# VFD_Ura_Controll.net
KiCad netlist of a schematic drawn in Altium Designer
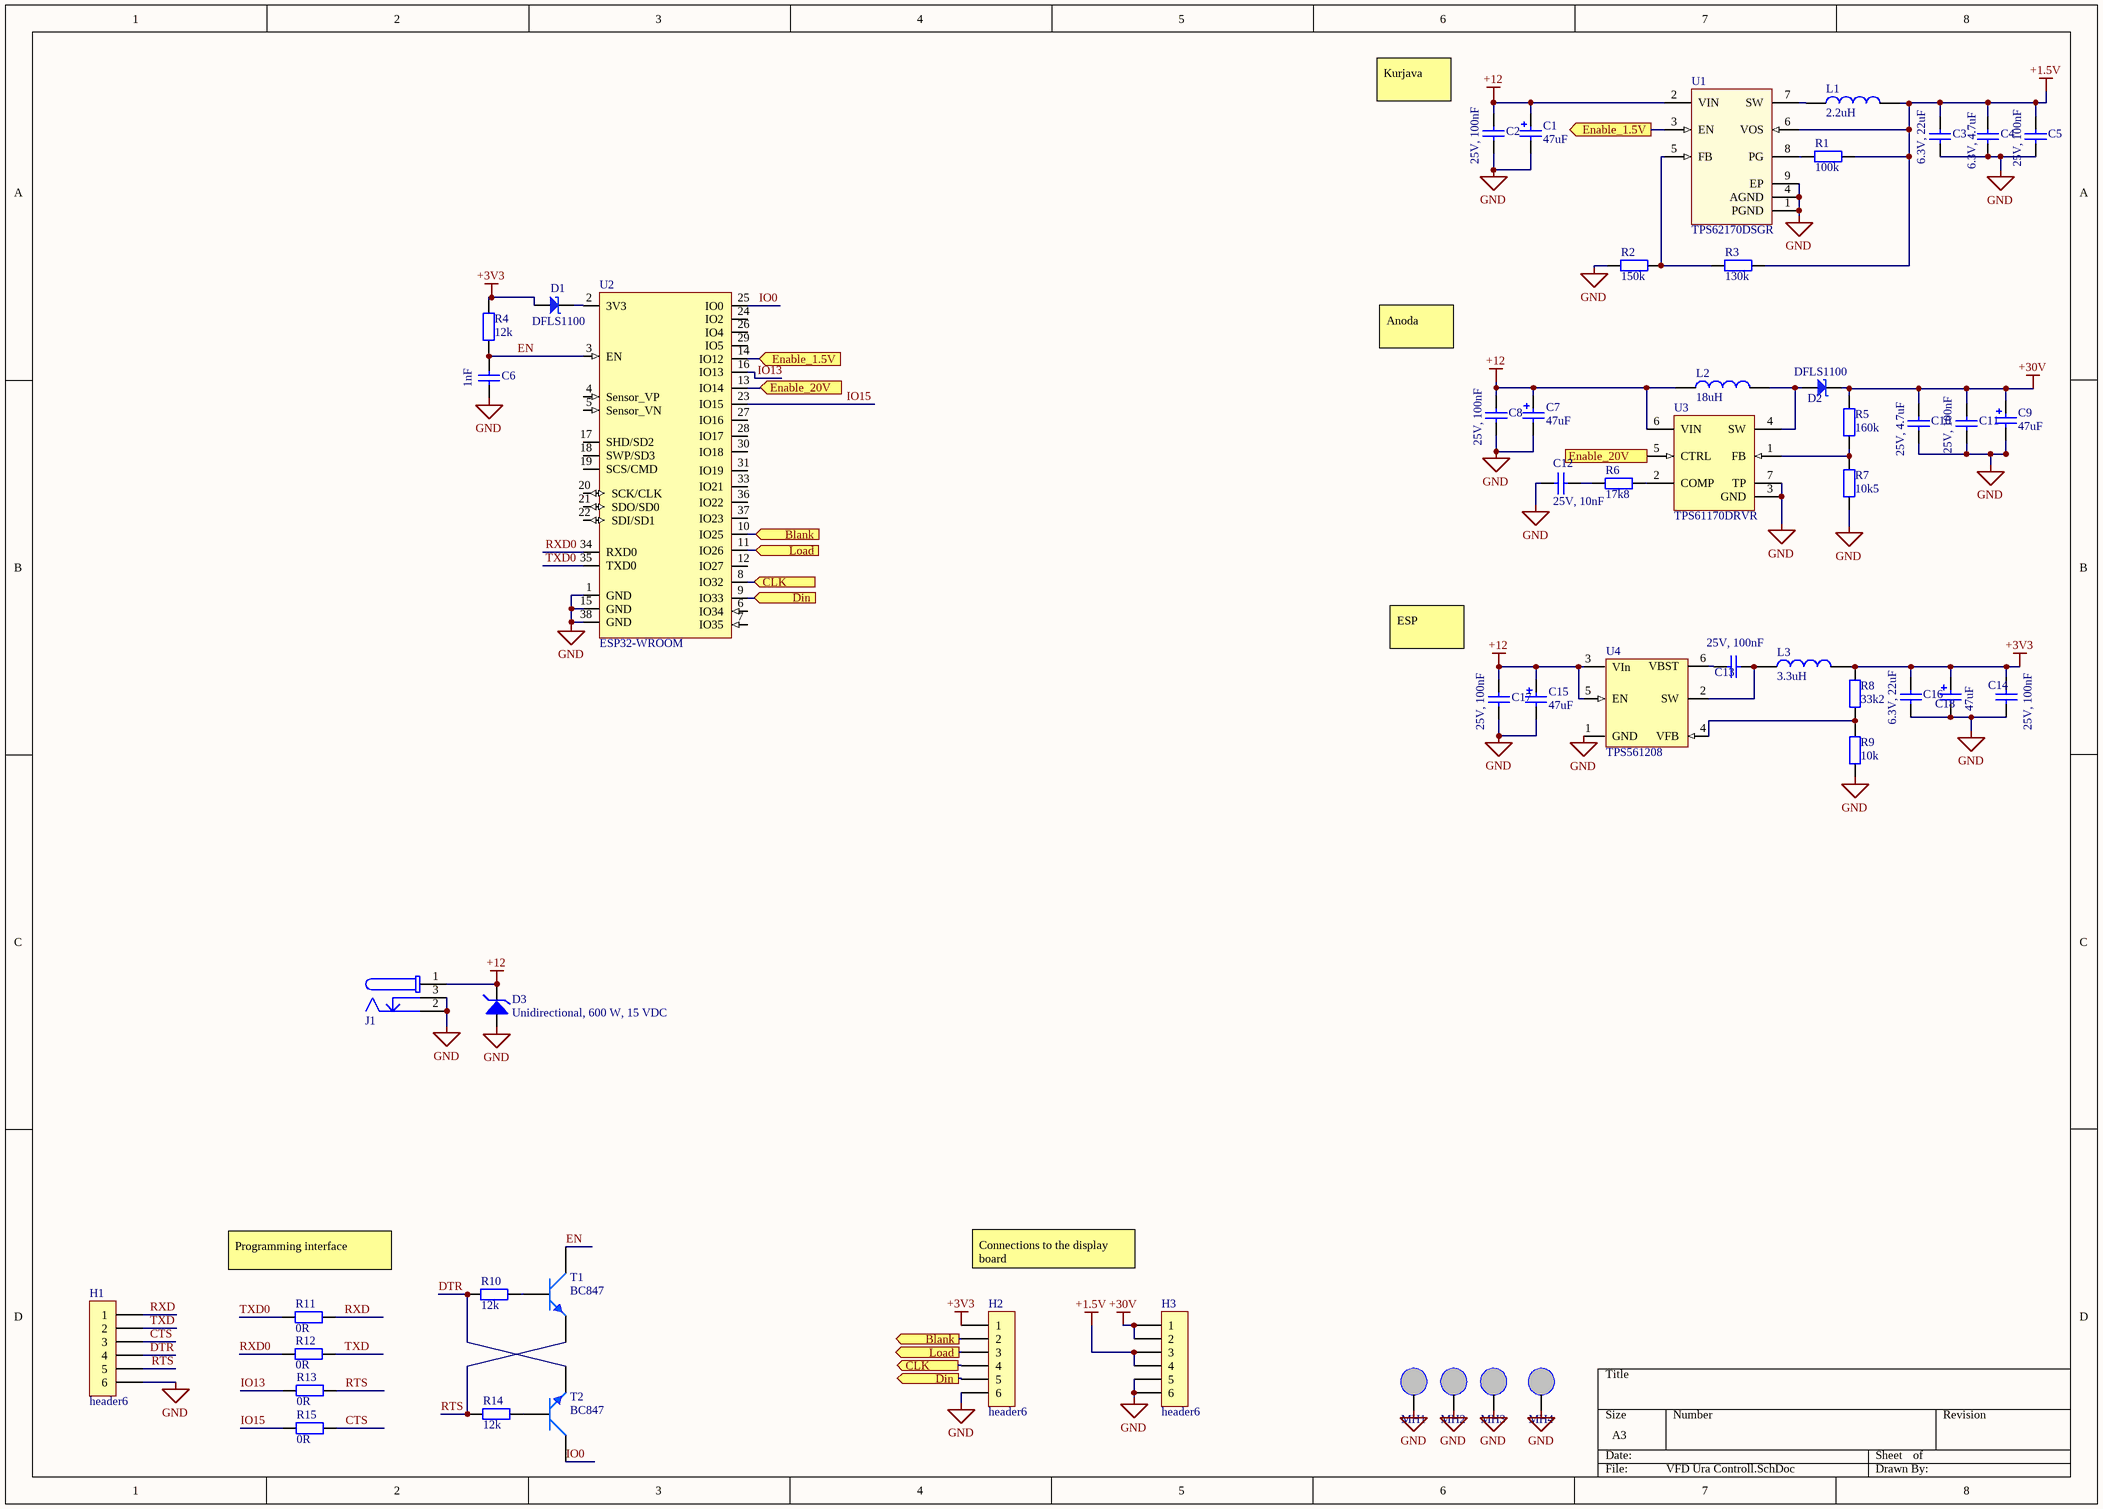
[diagram p0: VFD Ura Controll.SchDoc]

(export (version "E")
  (design (tool "Eeschema 10.0.6"))
  (components
    (comp (ref "C1")
      (value "47uF")
      (footprint "WCAP-PSLC_8x11.7")
      (description "WCAP-PSLC Aluminum Polymer Capacitors, size Ф8x11.7mm, 25V DC, 47uF")
      (fields (field (name "PART NUMBER") "875075555002") (field (name "PUBLISHER") "Wurth Elektronik"))
      (libsource (lib "ALTIUM-WCAP-PSLC-rev17b") (part "875075555002"))
    )
    (comp (ref "C2")
      (value "25V, 100nF")
      (footprint "0603_1.6x0.8x0.8mm_Reflow Soldering")
      (description "WCAP-CSGP Ceramic Capacitors, 0603, X7R, 25V, 100nF")
      (fields (field (name "PART NUMBER") "885012206071") (field (name "PUBLISHER") "Wurth Elektronik"))
      (libsource (lib "ALTIUM-WCAP-CSGP-0603-rev17b") (part "885012206071"))
    )
    (comp (ref "C3")
      (value "6.3V, 22uF")
      (footprint "0805_2x1.25x1.25mm_Reflow Soldering")
      (description "WCAP-CSGP Ceramic Capacitors, 0805, X5R, 6.3V, 22uF")
      (fields (field (name "PART NUMBER") "885012107005") (field (name "PUBLISHER") "Wurth Elektronik"))
      (libsource (lib "ALTIUM-WCAP-CSGP-0805-rev17b") (part "885012107005"))
    )
    (comp (ref "C4")
      (value "6.3V, 4.7uF")
      (footprint "0805_2x1.25x1.25mm_Reflow Soldering")
      (description "WCAP-CSGP Ceramic Capacitors, 0805, X5R, 6.3V, 4.7uF")
      (fields (field (name "PART NUMBER") "885012107003") (field (name "PUBLISHER") "Wurth Elektronik"))
      (libsource (lib "ALTIUM-WCAP-CSGP-0805-rev17b") (part "885012107003"))
    )
    (comp (ref "C5")
      (value "25V, 100nF")
      (footprint "0603_1.6x0.8x0.8mm_Reflow Soldering")
      (description "WCAP-CSGP Ceramic Capacitors, 0603, X7R, 25V, 100nF")
      (fields (field (name "PART NUMBER") "885012206071") (field (name "PUBLISHER") "Wurth Elektronik"))
      (libsource (lib "ALTIUM-WCAP-CSGP-0603-rev17b") (part "885012206071"))
    )
    (comp (ref "C6")
      (value "1nF")
      (footprint "0603_1.6x0.8x0.8mm_Reflow Soldering")
      (description "WCAP-CSGP Ceramic Capacitors, 0603, X7R, 25V, 100nF")
      (fields (field (name "PART NUMBER") "885012206071") (field (name "PUBLISHER") "Wurth Elektronik"))
      (libsource (lib "ALTIUM-WCAP-CSGP-0603-rev17b") (part "885012206071"))
    )
    (comp (ref "C7")
      (value "47uF")
      (footprint "WCAP-PSLC_8x11.7")
      (description "WCAP-PSLC Aluminum Polymer Capacitors, size Ф8x11.7mm, 25V DC, 47uF")
      (fields (field (name "PART NUMBER") "875075555002") (field (name "PUBLISHER") "Wurth Elektronik"))
      (libsource (lib "ALTIUM-WCAP-PSLC-rev17b") (part "875075555002"))
    )
    (comp (ref "C8")
      (value "25V, 100nF")
      (footprint "0603_1.6x0.8x0.8mm_Reflow Soldering")
      (description "WCAP-CSGP Ceramic Capacitors, 0603, X7R, 25V, 100nF")
      (fields (field (name "PART NUMBER") "885012206071") (field (name "PUBLISHER") "Wurth Elektronik"))
      (libsource (lib "ALTIUM-WCAP-CSGP-0603-rev17b") (part "885012206071"))
    )
    (comp (ref "C9")
      (value "47uF")
      (footprint "WCAP-PSLC_8x11.7")
      (description "WCAP-PSLC Aluminum Polymer Capacitors, size Ф8x11.7mm, 25V DC, 47uF")
      (fields (field (name "PART NUMBER") "875075555002") (field (name "PUBLISHER") "Wurth Elektronik"))
      (libsource (lib "ALTIUM-WCAP-PSLC-rev17b") (part "875075555002"))
    )
    (comp (ref "C10")
      (value "25V, 4.7uF")
      (footprint "0805_2x1.25x1.25mm_Reflow Soldering")
      (description "WCAP-CSGP Ceramic Capacitors, 0805, X5R, 25V, 4.7uF")
      (fields (field (name "PART NUMBER") "885012107018") (field (name "PUBLISHER") "Wurth Elektronik"))
      (libsource (lib "ALTIUM-WCAP-CSGP-0805-rev17b") (part "885012107018"))
    )
    (comp (ref "C11")
      (value "25V, 100nF")
      (footprint "0603_1.6x0.8x0.8mm_Reflow Soldering")
      (description "WCAP-CSGP Ceramic Capacitors, 0603, X7R, 25V, 100nF")
      (fields (field (name "PART NUMBER") "885012206071") (field (name "PUBLISHER") "Wurth Elektronik"))
      (libsource (lib "ALTIUM-WCAP-CSGP-0603-rev17b") (part "885012206071"))
    )
    (comp (ref "C12")
      (value "25V, 10nF")
      (footprint "0603_1.6x0.8x0.8mm_Reflow Soldering")
      (description "WCAP-CSGP Ceramic Capacitors, 0603, X7R, 25V, 10nF")
      (fields (field (name "PART NUMBER") "885012206065") (field (name "PUBLISHER") "Wurth Elektronik"))
      (libsource (lib "ALTIUM-WCAP-CSGP-0603-rev17b") (part "885012206065"))
    )
    (comp (ref "C13")
      (value "25V, 100nF")
      (footprint "0603_1.6x0.8x0.8mm_Reflow Soldering")
      (description "WCAP-CSGP Ceramic Capacitors, 0603, X7R, 25V, 100nF")
      (fields (field (name "PART NUMBER") "885012206071") (field (name "PUBLISHER") "Wurth Elektronik"))
      (libsource (lib "ALTIUM-WCAP-CSGP-0603-rev17b") (part "885012206071"))
    )
    (comp (ref "C14")
      (value "25V, 100nF")
      (footprint "0603_1.6x0.8x0.8mm_Reflow Soldering")
      (description "WCAP-CSGP Ceramic Capacitors, 0603, X7R, 25V, 100nF")
      (fields (field (name "PART NUMBER") "885012206071") (field (name "PUBLISHER") "Wurth Elektronik"))
      (libsource (lib "ALTIUM-WCAP-CSGP-0603-rev17b") (part "885012206071"))
    )
    (comp (ref "C15")
      (value "47uF")
      (footprint "WCAP-PSLC_8x11.7")
      (description "WCAP-PSLC Aluminum Polymer Capacitors, size Ф8x11.7mm, 25V DC, 47uF")
      (fields (field (name "PART NUMBER") "875075555002") (field (name "PUBLISHER") "Wurth Elektronik"))
      (libsource (lib "ALTIUM-WCAP-PSLC-rev17b") (part "875075555002"))
    )
    (comp (ref "C16")
      (value "6.3V, 22uF")
      (footprint "0805_2x1.25x1.25mm_Reflow Soldering")
      (description "WCAP-CSGP Ceramic Capacitors, 0805, X5R, 6.3V, 22uF")
      (fields (field (name "PART NUMBER") "885012107005") (field (name "PUBLISHER") "Wurth Elektronik"))
      (libsource (lib "ALTIUM-WCAP-CSGP-0805-rev17b") (part "885012107005"))
    )
    (comp (ref "C17")
      (value "25V, 100nF")
      (footprint "0603_1.6x0.8x0.8mm_Reflow Soldering")
      (description "WCAP-CSGP Ceramic Capacitors, 0603, X7R, 25V, 100nF")
      (fields (field (name "PART NUMBER") "885012206071") (field (name "PUBLISHER") "Wurth Elektronik"))
      (libsource (lib "ALTIUM-WCAP-CSGP-0603-rev17b") (part "885012206071"))
    )
    (comp (ref "C18")
      (value "47uF")
      (footprint "WCAP-PSLC_8x11.7")
      (description "WCAP-PSLC Aluminum Polymer Capacitors, size Ф8x11.7mm, 25V DC, 47uF")
      (fields (field (name "PART NUMBER") "875075555002") (field (name "PUBLISHER") "Wurth Elektronik"))
      (libsource (lib "ALTIUM-WCAP-PSLC-rev17b") (part "875075555002"))
    )
    (comp (ref "D1")
      (value "DFLS1100")
      (footprint "PowerDi123")
      (libsource (lib "Oblak Library") (part "DFLS1100"))
    )
    (comp (ref "D2")
      (value "DFLS1100")
      (footprint "PowerDi123")
      (libsource (lib "Oblak Library") (part "DFLS1100"))
    )
    (comp (ref "D3")
      (value "Unidirectional, 600 W, 15 VDC")
      (footprint "DO-214AA_Unidirectional")
      (description "WE-TVSP Power TVS Diode, Unidirectional, 600 W, 15 VDC")
      (fields
        (field (name "PARTNO") "824520151")
        (field (name "MANUFACTURER") "Wurth Elektronik")
        (field (name "CREATED BY") "Baojun Chen")
      )
      (libsource (lib "ALTIUM-WE-TVSP-rev15a") (part "WE-TVSP DO-214AA, 824520151"))
    )
    (comp (ref "H1") (value "header6") (footprint "Letev6") (libsource (lib "VolkD3D") (part "header6")))
    (comp (ref "H2") (value "header6") (footprint "Letev6") (libsource (lib "") (part "header6_1")))
    (comp (ref "H3") (value "header6") (footprint "Letev6") (libsource (lib "") (part "header6_1")))
    (comp (ref "J1")
      (value "694106301002")
      (footprint "694106301002")
      (description "DC Power Jack Right Angled(6.4) WR-DC")
      (fields (field (name "PUBLISHER") "Wurth Elektronik"))
      (libsource (lib "Altium_WR-DC_POWER_JACK_CONNECTORS (rev17a)") (part "694106301002"))
    )
    (comp (ref "L1")
      (value "2.2uH")
      (footprint "WE-TPC_2811")
      (description "WE-TPC SMD Shielded Tiny Power Inductor, size 2811, 1.3A, 125mΩ, 2.2uH")
      (fields (field (name "PART NUMBER") "744028002") (field (name "PUBLISHER") "Wurth Elektronik"))
      (libsource (lib "ALTIUM-WE-TPC-rev17a") (part "744028002"))
    )
    (comp (ref "L2")
      (value "18uH")
      (footprint "WE-TPC_4818")
      (description "WE-TPC SMD Shielded Tiny Power Inductor, size 4818, 0.92A, 270mΩ, 18uH")
      (fields (field (name "PART NUMBER") "744042180") (field (name "PUBLISHER") "Wurth Elektronik"))
      (libsource (lib "ALTIUM-WE-TPC-rev17a") (part "744042180"))
    )
    (comp (ref "L3")
      (value "3.3uH")
      (footprint "WE-TPC_2828")
      (description "WE-TPC SMD Shielded Tiny Power Inductor, size 2828, 1.5A, 85mΩ, 3.3uH")
      (fields (field (name "PART NUMBER") "744025003") (field (name "PUBLISHER") "Wurth Elektronik"))
      (libsource (lib "ALTIUM-WE-TPC-rev17a") (part "744025003"))
    )
    (comp (ref "MH1")
      (value "Mounting Hole M3")
      (footprint "Mounting Hole M3")
      (libsource (lib "Oblak Library") (part "Mounting Hole M3"))
    )
    (comp (ref "MH2")
      (value "Mounting Hole M3")
      (footprint "Mounting Hole M3")
      (libsource (lib "Oblak Library") (part "Mounting Hole M3"))
    )
    (comp (ref "MH3")
      (value "Mounting Hole M3")
      (footprint "Mounting Hole M3")
      (libsource (lib "Oblak Library") (part "Mounting Hole M3"))
    )
    (comp (ref "MH4")
      (value "Mounting Hole M3")
      (footprint "Mounting Hole M3")
      (libsource (lib "Oblak Library") (part "Mounting Hole M3"))
    )
    (comp (ref "R1")
      (value "100k")
      (footprint "RES0805_1")
      (fields (field (name "Comment") "Res2-smd"))
      (libsource (lib "VolkD3D") (part "Res2-smd"))
    )
    (comp (ref "R2")
      (value "150k")
      (footprint "RES0805_1")
      (fields (field (name "Comment") "Res2-smd"))
      (libsource (lib "VolkD3D") (part "Res2-smd"))
    )
    (comp (ref "R3")
      (value "130k")
      (footprint "RES0805_1")
      (fields (field (name "Comment") "Res2-smd"))
      (libsource (lib "VolkD3D") (part "Res2-smd"))
    )
    (comp (ref "R4") (value "12k") (footprint "RES0805_1") (libsource (lib "") (part "Res2-smd_1")))
    (comp (ref "R5")
      (value "160k")
      (footprint "RES0805_1")
      (fields (field (name "Comment") "Res2-smd"))
      (libsource (lib "") (part "Res2-smd_1"))
    )
    (comp (ref "R6")
      (value "17k8")
      (footprint "RES0805_1")
      (fields (field (name "Comment") "Res2-smd"))
      (libsource (lib "VolkD3D") (part "Res2-smd"))
    )
    (comp (ref "R7")
      (value "10k5")
      (footprint "RES0805_1")
      (fields (field (name "Comment") "Res2-smd"))
      (libsource (lib "") (part "Res2-smd_1"))
    )
    (comp (ref "R8")
      (value "33k2")
      (footprint "RES0805_1")
      (fields (field (name "Comment") "Res2-smd"))
      (libsource (lib "") (part "Res2-smd_1"))
    )
    (comp (ref "R9")
      (value "10k")
      (footprint "RES0805_1")
      (fields (field (name "Comment") "Res2-smd"))
      (libsource (lib "") (part "Res2-smd_1"))
    )
    (comp (ref "R10") (value "12k") (footprint "RES0805_1") (libsource (lib "") (part "Res2-smd_2")))
    (comp (ref "R11")
      (value "0R")
      (footprint "RES0805_1")
      (fields (field (name "Comment") "12k"))
      (libsource (lib "") (part "Res2-smd_2"))
    )
    (comp (ref "R12")
      (value "0R")
      (footprint "RES0805_1")
      (fields (field (name "Comment") "12k"))
      (libsource (lib "") (part "Res2-smd_2"))
    )
    (comp (ref "R13")
      (value "0R")
      (footprint "RES0805_1")
      (fields (field (name "Comment") "12k"))
      (libsource (lib "") (part "Res2-smd_2"))
    )
    (comp (ref "R14") (value "12k") (footprint "RES0805_1") (libsource (lib "") (part "Res2-smd_2")))
    (comp (ref "R15")
      (value "0R")
      (footprint "RES0805_1")
      (fields (field (name "Comment") "12k"))
      (libsource (lib "") (part "Res2-smd_2"))
    )
    (comp (ref "T1")
      (value "BC847")
      (footprint "SOT23")
      (description "45 V, 100 mA NPN general-purpose transistors")
      (libsource (lib "Oblak Library") (part "BC847"))
    )
    (comp (ref "T2")
      (value "BC847")
      (footprint "SOT23")
      (description "45 V, 100 mA NPN general-purpose transistors")
      (libsource (lib "Oblak Library") (part "BC847"))
    )
    (comp (ref "U1")
      (value "TPS62170DSGR")
      (footprint "DSG8-1600X900TP")
      (fields (field (name "MANUFACTURER") "Texas Instruments"))
      (libsource (lib "TI Power Management Step-Down Regulator") (part "TPS62170DSGR"))
    )
    (comp (ref "U2")
      (value "ESP32-WROOM")
      (footprint "ESP32-WROOM")
      (libsource (lib "IV-6") (part "ESP32-WROOM"))
    )
    (comp (ref "U3")
      (value "TPS61170DRVR")
      (footprint "DRV6-1600X1000TP")
      (fields (field (name "MANUFACTURER") "Texas Instruments"))
      (libsource (lib "TI Power Management Step-Up Regulator") (part "TPS61170DRVR"))
    )
    (comp (ref "U4")
      (value "TPS561208")
      (footprint "SOT23-6 TI")
      (libsource (lib "Oblak Library") (part "TPS561208"))
    )
  )
  (nets
    (net (code "1") (name "+1.5V") (class "Default")
      (node (ref "C3") (pin "2") (pinfunction "2_2") (pintype "passive"))
      (node (ref "C4") (pin "2") (pinfunction "2_2") (pintype "passive"))
      (node (ref "C5") (pin "2") (pinfunction "2_2") (pintype "passive"))
      (node (ref "H3") (pin "3") (pinfunction "3_3") (pintype "passive"))
      (node (ref "H3") (pin "4") (pinfunction "4_4") (pintype "passive"))
      (node (ref "L1") (pin "2") (pinfunction "2_2") (pintype "passive"))
      (node (ref "R1") (pin "2") (pinfunction "2_2") (pintype "passive"))
      (node (ref "R3") (pin "2") (pinfunction "2_2") (pintype "passive"))
      (node (ref "U1") (pin "6") (pinfunction "VOS_6") (pintype "input"))
    )
    (net (code "2") (name "+3V3") (class "Default")
      (node (ref "C14") (pin "2") (pinfunction "2_2") (pintype "passive"))
      (node (ref "C16") (pin "2") (pinfunction "2_2") (pintype "passive"))
      (node (ref "C18") (pin "1") (pinfunction "P_1") (pintype "passive"))
      (node (ref "D1") (pin "1") (pinfunction "A_1") (pintype "passive"))
      (node (ref "H2") (pin "1") (pinfunction "1_1") (pintype "passive"))
      (node (ref "L3") (pin "2") (pinfunction "2_2") (pintype "passive"))
      (node (ref "R4") (pin "2") (pinfunction "2_2") (pintype "passive"))
      (node (ref "R8") (pin "2") (pinfunction "2_2") (pintype "passive"))
    )
    (net (code "3") (name "+12") (class "Default")
      (node (ref "C1") (pin "1") (pinfunction "P_1") (pintype "passive"))
      (node (ref "C15") (pin "1") (pinfunction "P_1") (pintype "passive"))
      (node (ref "C17") (pin "2") (pinfunction "2_2") (pintype "passive"))
      (node (ref "C2") (pin "2") (pinfunction "2_2") (pintype "passive"))
      (node (ref "C7") (pin "1") (pinfunction "P_1") (pintype "passive"))
      (node (ref "C8") (pin "2") (pinfunction "2_2") (pintype "passive"))
      (node (ref "D3") (pin "1") (pinfunction "1_1") (pintype "passive"))
      (node (ref "J1") (pin "1") (pinfunction "1_1") (pintype "passive"))
      (node (ref "L2") (pin "1") (pinfunction "1_1") (pintype "passive"))
      (node (ref "U1") (pin "2") (pinfunction "VIN_2") (pintype "power_in"))
      (node (ref "U3") (pin "6") (pinfunction "VIN_6") (pintype "power_in"))
      (node (ref "U4") (pin "3") (pinfunction "VIn_3") (pintype "power_in"))
      (node (ref "U4") (pin "5") (pinfunction "EN_5") (pintype "input"))
    )
    (net (code "4") (name "+30V") (class "Default")
      (node (ref "C10") (pin "2") (pinfunction "2_2") (pintype "passive"))
      (node (ref "C11") (pin "2") (pinfunction "2_2") (pintype "passive"))
      (node (ref "C9") (pin "1") (pinfunction "P_1") (pintype "passive"))
      (node (ref "D2") (pin "2") (pinfunction "K_2") (pintype "passive"))
      (node (ref "H3") (pin "1") (pinfunction "1_1") (pintype "passive"))
      (node (ref "H3") (pin "2") (pinfunction "2_2") (pintype "passive"))
      (node (ref "R5") (pin "2") (pinfunction "2_2") (pintype "passive"))
    )
    (net (code "5") (name "/Blank") (class "Default")
      (node (ref "H2") (pin "2") (pinfunction "2_2") (pintype "passive"))
      (node (ref "U2") (pin "10") (pinfunction "IO25_10") (pintype "bidirectional"))
    )
    (net (code "6") (name "/CLK") (class "Default")
      (node (ref "H2") (pin "4") (pinfunction "4_4") (pintype "passive"))
      (node (ref "U2") (pin "8") (pinfunction "IO32_8") (pintype "bidirectional"))
    )
    (net (code "7") (name "/CTS") (class "Default")
      (node (ref "H1") (pin "3") (pinfunction "3_3") (pintype "passive"))
      (node (ref "R15") (pin "1") (pinfunction "1_1") (pintype "passive"))
    )
    (net (code "8") (name "/DTR") (class "Default")
      (node (ref "H1") (pin "4") (pinfunction "4_4") (pintype "passive"))
      (node (ref "R10") (pin "2") (pinfunction "2_2") (pintype "passive"))
      (node (ref "T2") (pin "2") (pinfunction "E_2") (pintype "passive"))
    )
    (net (code "9") (name "/Din") (class "Default")
      (node (ref "H2") (pin "5") (pinfunction "5_5") (pintype "passive"))
      (node (ref "U2") (pin "9") (pinfunction "IO33_9") (pintype "bidirectional"))
    )
    (net (code "10") (name "/EN") (class "Default")
      (node (ref "C6") (pin "2") (pinfunction "2_2") (pintype "passive"))
      (node (ref "R4") (pin "1") (pinfunction "1_1") (pintype "passive"))
      (node (ref "T1") (pin "3") (pinfunction "C_3") (pintype "passive"))
      (node (ref "U2") (pin "3") (pinfunction "EN_3") (pintype "input"))
    )
    (net (code "11") (name "/Enable_1.5V") (class "Default")
      (node (ref "U1") (pin "3") (pinfunction "EN_3") (pintype "input"))
      (node (ref "U2") (pin "14") (pinfunction "IO12_14") (pintype "bidirectional"))
    )
    (net (code "12") (name "/Enable_20V") (class "Default")
      (node (ref "U2") (pin "13") (pinfunction "IO14_13") (pintype "bidirectional"))
      (node (ref "U3") (pin "5") (pinfunction "CTRL_5") (pintype "input"))
    )
    (net (code "13") (name "/IO0") (class "Default")
      (node (ref "T2") (pin "3") (pinfunction "C_3") (pintype "passive"))
      (node (ref "U2") (pin "25") (pinfunction "IO0_25") (pintype "bidirectional"))
    )
    (net (code "14") (name "/IO13") (class "Default")
      (node (ref "R13") (pin "2") (pinfunction "2_2") (pintype "passive"))
      (node (ref "U2") (pin "16") (pinfunction "IO13_16") (pintype "bidirectional"))
    )
    (net (code "15") (name "/IO15") (class "Default")
      (node (ref "R15") (pin "2") (pinfunction "2_2") (pintype "passive"))
      (node (ref "U2") (pin "23") (pinfunction "IO15_23") (pintype "bidirectional"))
    )
    (net (code "16") (name "/Load") (class "Default")
      (node (ref "H2") (pin "3") (pinfunction "3_3") (pintype "passive"))
      (node (ref "U2") (pin "11") (pinfunction "IO26_11") (pintype "bidirectional"))
    )
    (net (code "17") (name "/RTS") (class "Default")
      (node (ref "H1") (pin "5") (pinfunction "5_5") (pintype "passive"))
      (node (ref "R13") (pin "1") (pinfunction "1_1") (pintype "passive"))
      (node (ref "R14") (pin "2") (pinfunction "2_2") (pintype "passive"))
      (node (ref "T1") (pin "2") (pinfunction "E_2") (pintype "passive"))
    )
    (net (code "18") (name "/RXD") (class "Default")
      (node (ref "H1") (pin "1") (pinfunction "1_1") (pintype "passive"))
      (node (ref "R11") (pin "1") (pinfunction "1_1") (pintype "passive"))
    )
    (net (code "19") (name "/RXD0") (class "Default")
      (node (ref "R12") (pin "2") (pinfunction "2_2") (pintype "passive"))
      (node (ref "U2") (pin "34") (pinfunction "RXD0_34") (pintype "bidirectional"))
    )
    (net (code "20") (name "/TXD") (class "Default")
      (node (ref "H1") (pin "2") (pinfunction "2_2") (pintype "passive"))
      (node (ref "R12") (pin "1") (pinfunction "1_1") (pintype "passive"))
    )
    (net (code "21") (name "/TXD0") (class "Default")
      (node (ref "R11") (pin "2") (pinfunction "2_2") (pintype "passive"))
      (node (ref "U2") (pin "35") (pinfunction "TXD0_35") (pintype "bidirectional"))
    )
    (net (code "22") (name "GND") (class "Default")
      (node (ref "C1") (pin "2") (pinfunction "N_2") (pintype "passive"))
      (node (ref "C10") (pin "1") (pinfunction "1_1") (pintype "passive"))
      (node (ref "C11") (pin "1") (pinfunction "1_1") (pintype "passive"))
      (node (ref "C12") (pin "1") (pinfunction "1_1") (pintype "passive"))
      (node (ref "C14") (pin "1") (pinfunction "1_1") (pintype "passive"))
      (node (ref "C15") (pin "2") (pinfunction "N_2") (pintype "passive"))
      (node (ref "C16") (pin "1") (pinfunction "1_1") (pintype "passive"))
      (node (ref "C17") (pin "1") (pinfunction "1_1") (pintype "passive"))
      (node (ref "C18") (pin "2") (pinfunction "N_2") (pintype "passive"))
      (node (ref "C2") (pin "1") (pinfunction "1_1") (pintype "passive"))
      (node (ref "C3") (pin "1") (pinfunction "1_1") (pintype "passive"))
      (node (ref "C4") (pin "1") (pinfunction "1_1") (pintype "passive"))
      (node (ref "C5") (pin "1") (pinfunction "1_1") (pintype "passive"))
      (node (ref "C6") (pin "1") (pinfunction "1_1") (pintype "passive"))
      (node (ref "C7") (pin "2") (pinfunction "N_2") (pintype "passive"))
      (node (ref "C8") (pin "1") (pinfunction "1_1") (pintype "passive"))
      (node (ref "C9") (pin "2") (pinfunction "N_2") (pintype "passive"))
      (node (ref "D3") (pin "2") (pinfunction "2_2") (pintype "passive"))
      (node (ref "H1") (pin "6") (pinfunction "6_6") (pintype "passive"))
      (node (ref "H2") (pin "6") (pinfunction "6_6") (pintype "passive"))
      (node (ref "H3") (pin "5") (pinfunction "5_5") (pintype "passive"))
      (node (ref "H3") (pin "6") (pinfunction "6_6") (pintype "passive"))
      (node (ref "J1") (pin "2") (pinfunction "2_2") (pintype "passive"))
      (node (ref "J1") (pin "3") (pinfunction "3_3") (pintype "passive"))
      (node (ref "MH1") (pin "1") (pintype "passive"))
      (node (ref "MH2") (pin "1") (pintype "passive"))
      (node (ref "MH3") (pin "1") (pintype "passive"))
      (node (ref "MH4") (pin "1") (pintype "passive"))
      (node (ref "R2") (pin "1") (pinfunction "1_1") (pintype "passive"))
      (node (ref "R7") (pin "1") (pinfunction "1_1") (pintype "passive"))
      (node (ref "R9") (pin "1") (pinfunction "1_1") (pintype "passive"))
      (node (ref "U1") (pin "1") (pinfunction "PGND_1") (pintype "power_in"))
      (node (ref "U1") (pin "4") (pinfunction "AGND_4") (pintype "power_in"))
      (node (ref "U1") (pin "9") (pinfunction "EP_9") (pintype "power_in"))
      (node (ref "U2") (pin "1") (pinfunction "GND_1") (pintype "power_in"))
      (node (ref "U2") (pin "15") (pinfunction "GND_15") (pintype "power_in"))
      (node (ref "U2") (pin "38") (pinfunction "GND_38") (pintype "power_in"))
      (node (ref "U3") (pin "3") (pinfunction "GND_3") (pintype "power_in"))
      (node (ref "U3") (pin "7") (pinfunction "TP_7") (pintype "power_in"))
      (node (ref "U4") (pin "1") (pinfunction "GND_1") (pintype "power_in"))
    )
    (net (code "23") (name "Net-(C12-Pad2)") (class "Default")
      (node (ref "C12") (pin "2") (pinfunction "2_2") (pintype "passive"))
      (node (ref "R6") (pin "1") (pinfunction "1_1") (pintype "passive"))
    )
    (net (code "24") (name "Net-(D1-K)") (class "Default")
      (node (ref "D1") (pin "2") (pinfunction "K_2") (pintype "passive"))
      (node (ref "U2") (pin "2") (pinfunction "3V3_2") (pintype "power_in"))
    )
    (net (code "25") (name "Net-(D2-A)") (class "Default")
      (node (ref "D2") (pin "1") (pinfunction "A_1") (pintype "passive"))
      (node (ref "L2") (pin "2") (pinfunction "2_2") (pintype "passive"))
      (node (ref "U3") (pin "4") (pinfunction "SW_4") (pintype "power_in"))
    )
    (net (code "26") (name "Net-(T1-B)") (class "Default")
      (node (ref "R10") (pin "1") (pinfunction "1_1") (pintype "passive"))
      (node (ref "T1") (pin "1") (pinfunction "B_1") (pintype "passive"))
    )
    (net (code "27") (name "Net-(T2-B)") (class "Default")
      (node (ref "R14") (pin "1") (pinfunction "1_1") (pintype "passive"))
      (node (ref "T2") (pin "1") (pinfunction "B_1") (pintype "passive"))
    )
    (net (code "28") (name "Net-(U1-FB)") (class "Default")
      (node (ref "R2") (pin "2") (pinfunction "2_2") (pintype "passive"))
      (node (ref "R3") (pin "1") (pinfunction "1_1") (pintype "passive"))
      (node (ref "U1") (pin "5") (pinfunction "FB_5") (pintype "input"))
    )
    (net (code "29") (name "Net-(U1-PG)") (class "Default")
      (node (ref "R1") (pin "1") (pinfunction "1_1") (pintype "passive"))
      (node (ref "U1") (pin "8") (pinfunction "PG_8") (pintype "tri_state"))
    )
    (net (code "30") (name "Net-(U1-SW)") (class "Default")
      (node (ref "L1") (pin "1") (pinfunction "1_1") (pintype "passive"))
      (node (ref "U1") (pin "7") (pinfunction "SW_7") (pintype "power_in"))
    )
    (net (code "31") (name "Net-(U3-COMP)") (class "Default")
      (node (ref "R6") (pin "2") (pinfunction "2_2") (pintype "passive"))
      (node (ref "U3") (pin "2") (pinfunction "COMP_2") (pintype "passive"))
    )
    (net (code "32") (name "Net-(U3-FB)") (class "Default")
      (node (ref "R5") (pin "1") (pinfunction "1_1") (pintype "passive"))
      (node (ref "R7") (pin "2") (pinfunction "2_2") (pintype "passive"))
      (node (ref "U3") (pin "1") (pinfunction "FB_1") (pintype "input"))
    )
    (net (code "33") (name "Net-(U4-SW)") (class "Default")
      (node (ref "C13") (pin "1") (pinfunction "1_1") (pintype "passive"))
      (node (ref "L3") (pin "1") (pinfunction "1_1") (pintype "passive"))
      (node (ref "U4") (pin "2") (pinfunction "SW_2") (pintype "passive"))
    )
    (net (code "34") (name "Net-(U4-VBST)") (class "Default")
      (node (ref "C13") (pin "2") (pinfunction "2_2") (pintype "passive"))
      (node (ref "U4") (pin "6") (pinfunction "VBST_6") (pintype "passive"))
    )
    (net (code "35") (name "Net-(U4-VFB)") (class "Default")
      (node (ref "R8") (pin "1") (pinfunction "1_1") (pintype "passive"))
      (node (ref "R9") (pin "2") (pinfunction "2_2") (pintype "passive"))
      (node (ref "U4") (pin "4") (pinfunction "VFB_4") (pintype "input"))
    )
    (net (code "36") (name "unconnected-(U2-IO2-Pad24)") (class "Default")
      (node (ref "U2") (pin "24") (pinfunction "IO2_24") (pintype "bidirectional"))
    )
    (net (code "37") (name "unconnected-(U2-IO4-Pad26)") (class "Default")
      (node (ref "U2") (pin "26") (pinfunction "IO4_26") (pintype "bidirectional"))
    )
    (net (code "38") (name "unconnected-(U2-IO5-Pad29)") (class "Default")
      (node (ref "U2") (pin "29") (pinfunction "IO5_29") (pintype "bidirectional"))
    )
    (net (code "39") (name "unconnected-(U2-IO16-Pad27)") (class "Default")
      (node (ref "U2") (pin "27") (pinfunction "IO16_27") (pintype "bidirectional"))
    )
    (net (code "40") (name "unconnected-(U2-IO17-Pad28)") (class "Default")
      (node (ref "U2") (pin "28") (pinfunction "IO17_28") (pintype "bidirectional"))
    )
    (net (code "41") (name "unconnected-(U2-IO18-Pad30)") (class "Default")
      (node (ref "U2") (pin "30") (pinfunction "IO18_30") (pintype "bidirectional"))
    )
    (net (code "42") (name "unconnected-(U2-IO19-Pad31)") (class "Default")
      (node (ref "U2") (pin "31") (pinfunction "IO19_31") (pintype "bidirectional"))
    )
    (net (code "43") (name "unconnected-(U2-IO21-Pad33)") (class "Default")
      (node (ref "U2") (pin "33") (pinfunction "IO21_33") (pintype "bidirectional"))
    )
    (net (code "44") (name "unconnected-(U2-IO22-Pad36)") (class "Default")
      (node (ref "U2") (pin "36") (pinfunction "IO22_36") (pintype "bidirectional"))
    )
    (net (code "45") (name "unconnected-(U2-IO23-Pad37)") (class "Default")
      (node (ref "U2") (pin "37") (pinfunction "IO23_37") (pintype "bidirectional"))
    )
    (net (code "46") (name "unconnected-(U2-IO27-Pad12)") (class "Default")
      (node (ref "U2") (pin "12") (pinfunction "IO27_12") (pintype "bidirectional"))
    )
    (net (code "47") (name "unconnected-(U2-IO34-Pad6)") (class "Default")
      (node (ref "U2") (pin "6") (pinfunction "IO34_6") (pintype "input"))
    )
    (net (code "48") (name "unconnected-(U2-IO35-Pad7)") (class "Default")
      (node (ref "U2") (pin "7") (pinfunction "IO35_7") (pintype "input"))
    )
    (net (code "49") (name "unconnected-(U2-SCK{slash}CLK-Pad20)") (class "Default")
      (node (ref "U2") (pin "20") (pinfunction "SCK/CLK_20") (pintype "bidirectional"))
    )
    (net (code "50") (name "unconnected-(U2-SCS{slash}CMD-Pad19)") (class "Default")
      (node (ref "U2") (pin "19") (pinfunction "SCS/CMD_19") (pintype "bidirectional"))
    )
    (net (code "51") (name "unconnected-(U2-SDI{slash}SD1-Pad22)") (class "Default")
      (node (ref "U2") (pin "22") (pinfunction "SDI/SD1_22") (pintype "bidirectional"))
    )
    (net (code "52") (name "unconnected-(U2-SDO{slash}SD0-Pad21)") (class "Default")
      (node (ref "U2") (pin "21") (pinfunction "SDO/SD0_21") (pintype "bidirectional"))
    )
    (net (code "53") (name "unconnected-(U2-SHD{slash}SD2-Pad17)") (class "Default")
      (node (ref "U2") (pin "17") (pinfunction "SHD/SD2_17") (pintype "bidirectional"))
    )
    (net (code "54") (name "unconnected-(U2-SWP{slash}SD3-Pad18)") (class "Default")
      (node (ref "U2") (pin "18") (pinfunction "SWP/SD3_18") (pintype "bidirectional"))
    )
    (net (code "55") (name "unconnected-(U2-Sensor_VN-Pad5)") (class "Default")
      (node (ref "U2") (pin "5") (pinfunction "Sensor_VN_5") (pintype "input"))
    )
    (net (code "56") (name "unconnected-(U2-Sensor_VP-Pad4)") (class "Default")
      (node (ref "U2") (pin "4") (pinfunction "Sensor_VP_4") (pintype "input"))
    )
  )
)
